# Baro_Mag.net
KiCad netlist of a schematic drawn in Altium Designer
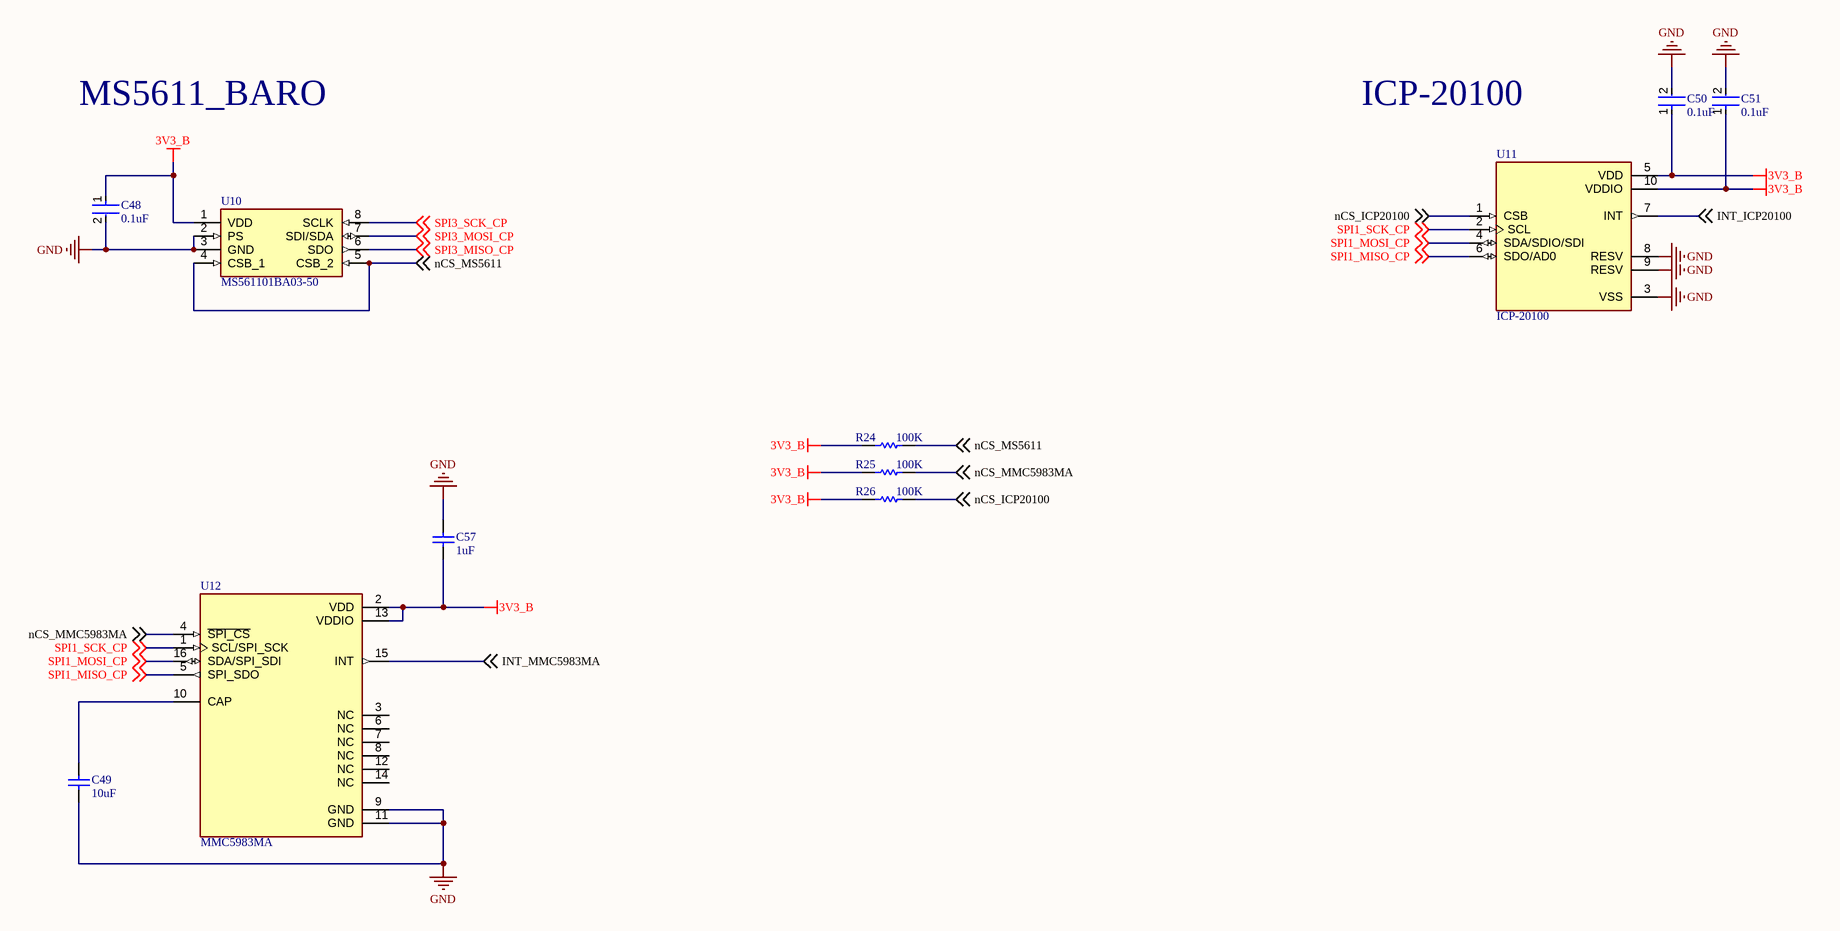
[diagram p0: Baro_Mag.SchDoc]

(export (version "E")
  (design (tool "Eeschema 10.0.6"))
  (components
    (comp (ref "C48")
      (value "0.1uF")
      (footprint "FP-C0603C-CF-MFG")
      (description "CAP CER 0.1UF 50V X7R 0603")
      (fields (field (name "TOLERANCE") "0.1") (field (name "MANUFACTURER") "KEMET"))
      (libsource (lib "Altium Content Vault") (part "b4654b650e69147ec39a6b967a45e02"))
    )
    (comp (ref "C49")
      (value "10uF")
      (footprint "CAPC2013X145X50LL20T25")
      (fields (field (name "MANUFACTURER") "Kemet") (field (name "PART NUMBER") "C0805C106K8RACTU"))
      (libsource (lib "Altium Content Vault") (part "CAP"))
    )
    (comp (ref "C50")
      (value "0.1uF")
      (footprint "FP-C0603C-CF-MFG")
      (description "CAP CER 0.1UF 50V X7R 0603")
      (fields (field (name "TOLERANCE") "0.1") (field (name "MANUFACTURER") "KEMET"))
      (libsource (lib "Altium Content Vault") (part "b4654b650e69147ec39a6b967a45e02"))
    )
    (comp (ref "C51")
      (value "0.1uF")
      (footprint "FP-C0603C-CF-MFG")
      (description "CAP CER 0.1UF 50V X7R 0603")
      (fields (field (name "TOLERANCE") "0.1") (field (name "MANUFACTURER") "KEMET"))
      (libsource (lib "Altium Content Vault") (part "b4654b650e69147ec39a6b967a45e02"))
    )
    (comp (ref "C57")
      (value "1uF")
      (footprint "CAPC1608X90X35LL15T15")
      (fields (field (name "MANUFACTURER") "Kemet") (field (name "PART NUMBER") "C0603C105K4RACTU"))
      (libsource (lib "Altium Content Vault") (part "CAP"))
    )
    (comp (ref "R24")
      (value "100K")
      (footprint "RESC1608X55X30ML20T10")
      (fields (field (name "PART NUMBER") "RK73B1JTTD104J") (field (name "MANUFACTURER") "KOA Speer"))
      (libsource (lib "Altium Content Vault") (part "RES"))
    )
    (comp (ref "R25")
      (value "100K")
      (footprint "RESC1608X55X30ML20T10")
      (fields (field (name "PART NUMBER") "RK73B1JTTD104J") (field (name "MANUFACTURER") "KOA Speer"))
      (libsource (lib "Altium Content Vault") (part "RES"))
    )
    (comp (ref "R26")
      (value "100K")
      (footprint "RESC1608X55X30ML20T10")
      (fields (field (name "PART NUMBER") "RK73B1JTTD104J") (field (name "MANUFACTURER") "KOA Speer"))
      (libsource (lib "Altium Content Vault") (part "RES"))
    )
    (comp (ref "U10")
      (value "MS561101BA03-50")
      (footprint "SamacSys:MS561101BA03-50")
      (description "Integrated Circuit")
      (fields (field (name "MOUSER PART NUMBER") "824-MS561101BA03-50"))
      (libsource (lib "*") (part "MS561101BA03-50"))
    )
    (comp (ref "U11")
      (value "ICP-20100")
      (footprint "PQFN50P200X200X85-10N")
      (fields (field (name "MF") "TDK InvenSense"))
      (libsource (lib "Hitesh Bhoyar") (part "ICP-20100"))
    )
    (comp (ref "U12")
      (value "MMC5983MA")
      (footprint "PQFN50P300X300X100-16N")
      (description "MMC5983 series Magnetic, Magnetometer Sensor Evaluation Board")
      (fields (field (name "MF") "Memsic Inc."))
      (libsource (lib "Hitesh Bhoyar") (part "MMC5983MA"))
    )
  )
  (nets
    (net (code "1") (name "3V3_B") (class "Default")
      (node (ref "C48") (pin "1") (pinfunction "1_1") (pintype "passive"))
      (node (ref "C50") (pin "1") (pinfunction "1_1") (pintype "passive"))
      (node (ref "C51") (pin "1") (pinfunction "1_1") (pintype "passive"))
      (node (ref "C57") (pin "1") (pinfunction "1_1") (pintype "passive"))
      (node (ref "R24") (pin "2") (pinfunction "2_2") (pintype "passive"))
      (node (ref "R25") (pin "2") (pinfunction "2_2") (pintype "passive"))
      (node (ref "R26") (pin "2") (pinfunction "2_2") (pintype "passive"))
      (node (ref "U10") (pin "1") (pinfunction "VDD_1") (pintype "power_in"))
      (node (ref "U11") (pin "10") (pinfunction "VDDIO_10") (pintype "power_in"))
      (node (ref "U11") (pin "5") (pinfunction "VDD_5") (pintype "power_in"))
      (node (ref "U12") (pin "13") (pinfunction "VDDIO_13") (pintype "power_in"))
      (node (ref "U12") (pin "2") (pinfunction "VDD_2") (pintype "power_in"))
    )
    (net (code "2") (name "GND") (class "Default")
      (node (ref "C48") (pin "2") (pinfunction "2_2") (pintype "passive"))
      (node (ref "C49") (pin "2") (pinfunction "2_2") (pintype "passive"))
      (node (ref "C50") (pin "2") (pinfunction "2_2") (pintype "passive"))
      (node (ref "C51") (pin "2") (pinfunction "2_2") (pintype "passive"))
      (node (ref "C57") (pin "2") (pinfunction "2_2") (pintype "passive"))
      (node (ref "U10") (pin "2") (pinfunction "PS_2") (pintype "input"))
      (node (ref "U10") (pin "3") (pinfunction "GND_3") (pintype "power_in"))
      (node (ref "U11") (pin "3") (pinfunction "VSS_3") (pintype "power_in"))
      (node (ref "U11") (pin "8") (pinfunction "RESV_8") (pintype "passive"))
      (node (ref "U11") (pin "9") (pinfunction "RESV_9") (pintype "passive"))
      (node (ref "U12") (pin "11") (pinfunction "GND_11") (pintype "power_in"))
      (node (ref "U12") (pin "9") (pinfunction "GND_9") (pintype "power_in"))
    )
    (net (code "3") (name "INT_ICP20100") (class "Default")
      (node (ref "U11") (pin "7") (pinfunction "INT_7") (pintype "output"))
    )
    (net (code "4") (name "INT_MMC5983MA") (class "Default")
      (node (ref "U12") (pin "15") (pinfunction "INT_15") (pintype "output"))
    )
    (net (code "5") (name "Net-(U12-CAP)") (class "Default")
      (node (ref "C49") (pin "1") (pinfunction "1_1") (pintype "passive"))
      (node (ref "U12") (pin "10") (pinfunction "CAP_10") (pintype "passive"))
    )
    (net (code "6") (name "SPI1_MISO_CP") (class "Default")
      (node (ref "U11") (pin "6") (pinfunction "SDO/AD0_6") (pintype "bidirectional"))
      (node (ref "U12") (pin "5") (pinfunction "SPI_SDO_5") (pintype "output"))
    )
    (net (code "7") (name "SPI1_MOSI_CP") (class "Default")
      (node (ref "U11") (pin "4") (pinfunction "SDA/SDIO/SDI_4") (pintype "bidirectional"))
      (node (ref "U12") (pin "16") (pinfunction "SDA/SPI_SDI_16") (pintype "bidirectional"))
    )
    (net (code "8") (name "SPI1_SCK_CP") (class "Default")
      (node (ref "U11") (pin "2") (pinfunction "SCL_2") (pintype "input"))
      (node (ref "U12") (pin "1") (pinfunction "SCL/SPI_SCK_1") (pintype "input"))
    )
    (net (code "9") (name "SPI3_MISO_CP") (class "Default")
      (node (ref "U10") (pin "6") (pinfunction "SDO_6") (pintype "output"))
    )
    (net (code "10") (name "SPI3_MOSI_CP") (class "Default")
      (node (ref "U10") (pin "7") (pinfunction "SDI/SDA_7") (pintype "bidirectional"))
    )
    (net (code "11") (name "SPI3_SCK_CP") (class "Default")
      (node (ref "U10") (pin "8") (pinfunction "SCLK_8") (pintype "input"))
    )
    (net (code "12") (name "nCS_ICP20100") (class "Default")
      (node (ref "R26") (pin "1") (pinfunction "1_1") (pintype "passive"))
      (node (ref "U11") (pin "1") (pinfunction "CSB_1") (pintype "input"))
    )
    (net (code "13") (name "nCS_MMC5983MA") (class "Default")
      (node (ref "R25") (pin "1") (pinfunction "1_1") (pintype "passive"))
      (node (ref "U12") (pin "4") (pinfunction "~{SPI_CS}_4") (pintype "input"))
    )
    (net (code "14") (name "nCS_MS5611") (class "Default")
      (node (ref "R24") (pin "1") (pinfunction "1_1") (pintype "passive"))
      (node (ref "U10") (pin "4") (pinfunction "CSB_1_4") (pintype "input"))
      (node (ref "U10") (pin "5") (pinfunction "CSB_2_5") (pintype "input"))
    )
    (net (code "15") (name "unconnected-(U12-NC-Pad3)") (class "Default")
      (node (ref "U12") (pin "3") (pinfunction "NC_3") (pintype "passive"))
    )
    (net (code "16") (name "unconnected-(U12-NC-Pad6)") (class "Default")
      (node (ref "U12") (pin "6") (pinfunction "NC_6") (pintype "passive"))
    )
    (net (code "17") (name "unconnected-(U12-NC-Pad7)") (class "Default")
      (node (ref "U12") (pin "7") (pinfunction "NC_7") (pintype "passive"))
    )
    (net (code "18") (name "unconnected-(U12-NC-Pad8)") (class "Default")
      (node (ref "U12") (pin "8") (pinfunction "NC_8") (pintype "passive"))
    )
    (net (code "19") (name "unconnected-(U12-NC-Pad12)") (class "Default")
      (node (ref "U12") (pin "12") (pinfunction "NC_12") (pintype "passive"))
    )
    (net (code "20") (name "unconnected-(U12-NC-Pad14)") (class "Default")
      (node (ref "U12") (pin "14") (pinfunction "NC_14") (pintype "passive"))
    )
  )
)
